# Sensores.net
KiCad netlist of a schematic drawn in EasyEDA Pro
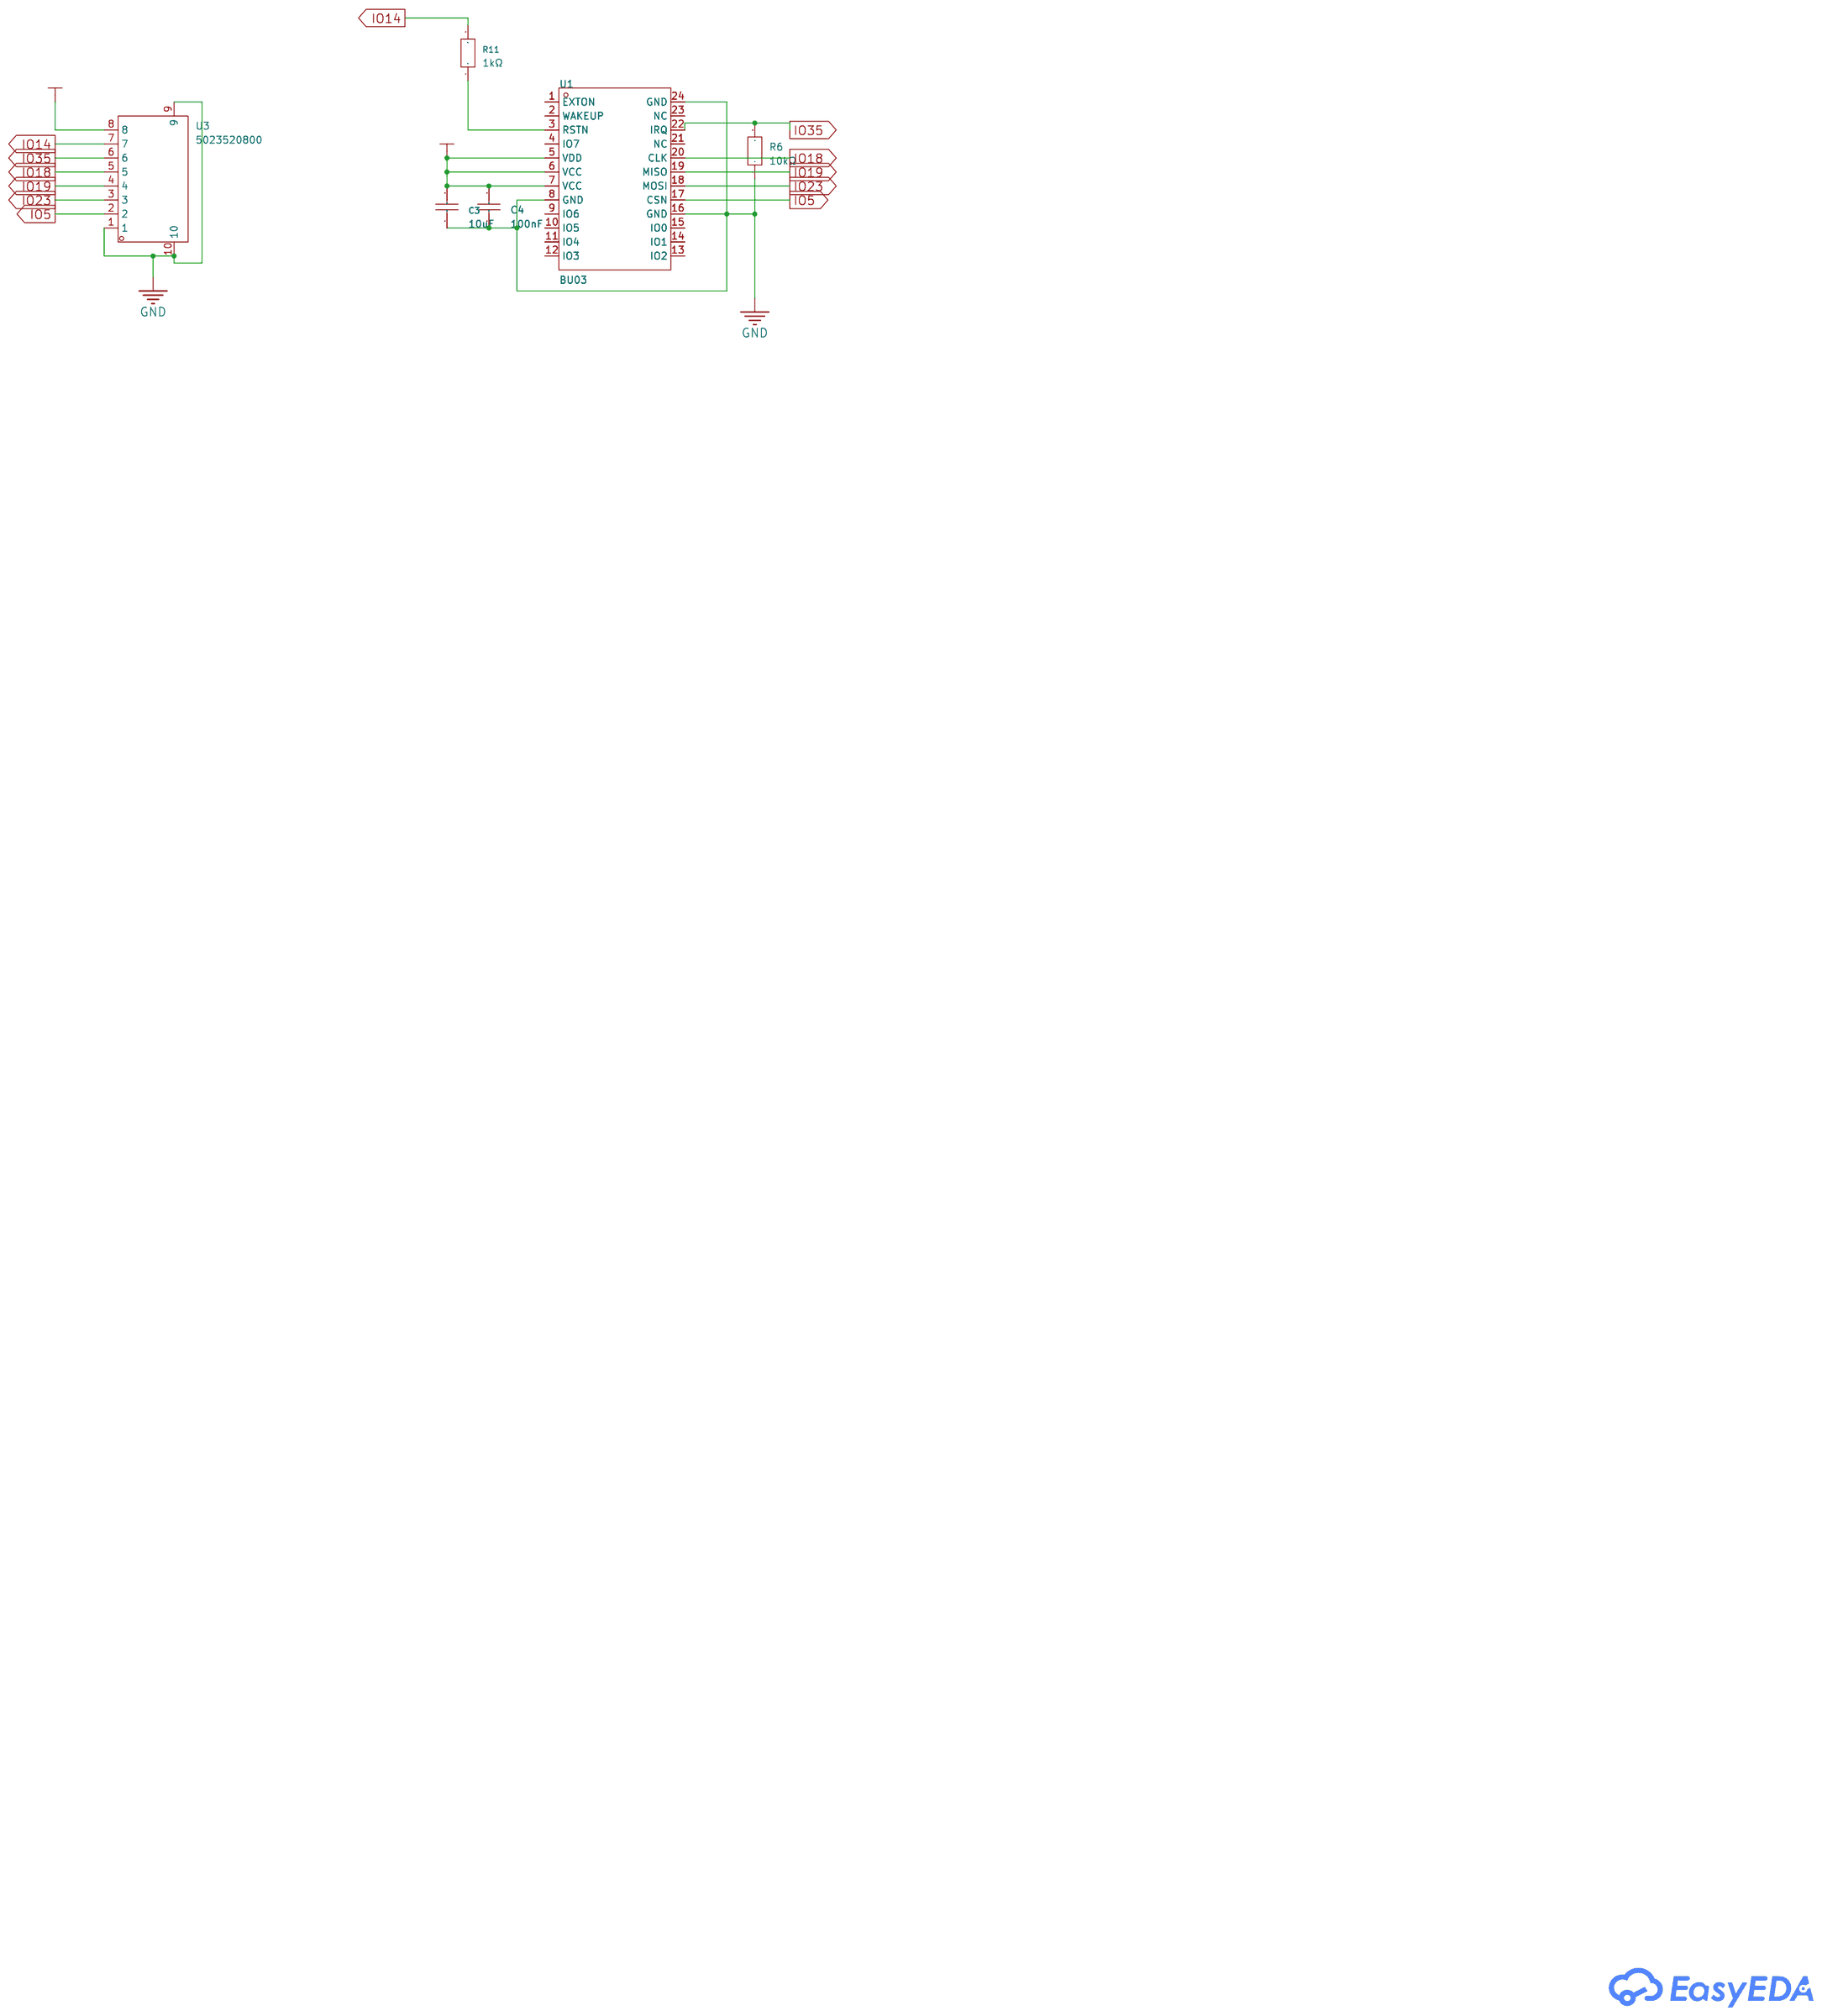
[diagram p0: schematic sheet]

(export (version "E")
  (design (tool "Eeschema 10.0.6"))
  (components
    (comp (ref "C3")
      (value "10uF")
      (footprint "easyedapro:C0805")
      (fields
        (field (name "Manufacturer Part") "CL21A106KPFNNNE")
        (field (name "Manufacturer") "SAMSUNG(三星)")
      )
      (libsource (lib "easyedapro") (part "CL21A106KPFNNNE"))
    )
    (comp (ref "C4")
      (value "100nF")
      (footprint "easyedapro:C0805")
      (description "Capacitance:100nF Tolerance:±5% Tolerance:±5% Voltage Rating:50V Temperature Coefficient:X7R")
      (fields (field (name "Manufacturer Part") "0805B104J500NT") (field (name "Manufacturer") "FH(风华)"))
      (libsource (lib "easyedapro") (part "0805B104J500NT"))
    )
    (comp (ref "R6")
      (value "10kΩ")
      (footprint "easyedapro:R0805")
      (fields (field (name "Manufacturer Part") "ERJP06F1002V") (field (name "Manufacturer") "PANASONIC(松下)"))
      (libsource (lib "easyedapro") (part "ERJP06F1002V"))
    )
    (comp (ref "R11")
      (value "1kΩ")
      (footprint "easyedapro:R0805")
      (fields (field (name "Manufacturer Part") "ERJP06F1001V") (field (name "Manufacturer") "PANASONIC(松下)"))
      (libsource (lib "easyedapro") (part "ERJP06F1001V"))
    )
    (comp (ref "U1")
      (value "BU03")
      (footprint "easyedapro:WIRELM-SMD_BU03")
      (fields (field (name "Manufacturer") "Ai-Thinker(安信可)"))
      (libsource (lib "easyedapro") (part "BU03"))
    )
    (comp (ref "U3")
      (value "5023520800")
      (footprint "easyedapro:CONN-SMD_5023520800")
      (fields (field (name "Manufacturer") "MOLEX"))
      (libsource (lib "easyedapro") (part "5023520800"))
    )
  )
  (nets
    (net (code "1") (name "+3V3") (class "Default")
      (node (ref "C3") (pin "2") (pinfunction "2_2") (pintype "input"))
      (node (ref "C4") (pin "2") (pinfunction "2_2") (pintype "input"))
      (node (ref "U1") (pin "5") (pinfunction "VDD_5") (pintype "unspecified"))
      (node (ref "U1") (pin "6") (pinfunction "VCC_6") (pintype "unspecified"))
      (node (ref "U1") (pin "7") (pinfunction "VCC_7") (pintype "unspecified"))
      (node (ref "U3") (pin "8") (pinfunction "8_8") (pintype "unspecified"))
    )
    (net (code "2") (name "GND") (class "Default")
      (node (ref "C3") (pin "1") (pinfunction "1_1") (pintype "input"))
      (node (ref "C4") (pin "1") (pinfunction "1_1") (pintype "input"))
      (node (ref "R6") (pin "1") (pinfunction "1_1") (pintype "unspecified"))
      (node (ref "U1") (pin "16") (pinfunction "GND_16") (pintype "unspecified"))
      (node (ref "U1") (pin "24") (pinfunction "GND_24") (pintype "unspecified"))
      (node (ref "U1") (pin "8") (pinfunction "GND_8") (pintype "unspecified"))
      (node (ref "U3") (pin "1") (pinfunction "1_1") (pintype "unspecified"))
      (node (ref "U3") (pin "10") (pinfunction "10_10") (pintype "unspecified"))
      (node (ref "U3") (pin "9") (pinfunction "9_9") (pintype "unspecified"))
    )
    (net (code "3") (name "IO5") (class "Default")
      (node (ref "U1") (pin "17") (pinfunction "CSN_17") (pintype "unspecified"))
      (node (ref "U3") (pin "2") (pinfunction "2_2") (pintype "unspecified"))
    )
    (net (code "4") (name "IO14") (class "Default")
      (node (ref "R11") (pin "2") (pinfunction "2_2") (pintype "input"))
      (node (ref "U3") (pin "7") (pinfunction "7_7") (pintype "unspecified"))
    )
    (net (code "5") (name "IO18") (class "Default")
      (node (ref "U1") (pin "20") (pinfunction "CLK_20") (pintype "unspecified"))
      (node (ref "U3") (pin "5") (pinfunction "5_5") (pintype "unspecified"))
    )
    (net (code "6") (name "IO19") (class "Default")
      (node (ref "U1") (pin "19") (pinfunction "MISO_19") (pintype "unspecified"))
      (node (ref "U3") (pin "4") (pinfunction "4_4") (pintype "unspecified"))
    )
    (net (code "7") (name "IO23") (class "Default")
      (node (ref "U1") (pin "18") (pinfunction "MOSI_18") (pintype "unspecified"))
      (node (ref "U3") (pin "3") (pinfunction "3_3") (pintype "unspecified"))
    )
    (net (code "8") (name "IO35") (class "Default")
      (node (ref "R6") (pin "2") (pinfunction "2_2") (pintype "unspecified"))
      (node (ref "U1") (pin "22") (pinfunction "IRQ_22") (pintype "unspecified"))
      (node (ref "U3") (pin "6") (pinfunction "6_6") (pintype "unspecified"))
    )
    (net (code "9") (name "Net-(U1-RSTN)") (class "Default")
      (node (ref "R11") (pin "1") (pinfunction "1_1") (pintype "input"))
      (node (ref "U1") (pin "3") (pinfunction "RSTN_3") (pintype "unspecified"))
    )
    (net (code "10") (name "unconnected-(U1-EXTON-Pad1)") (class "Default")
      (node (ref "U1") (pin "1") (pinfunction "EXTON_1") (pintype "unspecified"))
    )
    (net (code "11") (name "unconnected-(U1-IO0-Pad15)") (class "Default")
      (node (ref "U1") (pin "15") (pinfunction "IO0_15") (pintype "unspecified"))
    )
    (net (code "12") (name "unconnected-(U1-IO1-Pad14)") (class "Default")
      (node (ref "U1") (pin "14") (pinfunction "IO1_14") (pintype "unspecified"))
    )
    (net (code "13") (name "unconnected-(U1-IO2-Pad13)") (class "Default")
      (node (ref "U1") (pin "13") (pinfunction "IO2_13") (pintype "unspecified"))
    )
    (net (code "14") (name "unconnected-(U1-IO3-Pad12)") (class "Default")
      (node (ref "U1") (pin "12") (pinfunction "IO3_12") (pintype "unspecified"))
    )
    (net (code "15") (name "unconnected-(U1-IO4-Pad11)") (class "Default")
      (node (ref "U1") (pin "11") (pinfunction "IO4_11") (pintype "unspecified"))
    )
    (net (code "16") (name "unconnected-(U1-IO5-Pad10)") (class "Default")
      (node (ref "U1") (pin "10") (pinfunction "IO5_10") (pintype "unspecified"))
    )
    (net (code "17") (name "unconnected-(U1-IO6-Pad9)") (class "Default")
      (node (ref "U1") (pin "9") (pinfunction "IO6_9") (pintype "unspecified"))
    )
    (net (code "18") (name "unconnected-(U1-IO7-Pad4)") (class "Default")
      (node (ref "U1") (pin "4") (pinfunction "IO7_4") (pintype "unspecified"))
    )
    (net (code "19") (name "unconnected-(U1-NC-Pad21)") (class "Default")
      (node (ref "U1") (pin "21") (pinfunction "NC_21") (pintype "unspecified"))
    )
    (net (code "20") (name "unconnected-(U1-NC-Pad23)") (class "Default")
      (node (ref "U1") (pin "23") (pinfunction "NC_23") (pintype "unspecified"))
    )
    (net (code "21") (name "unconnected-(U1-WAKEUP-Pad2)") (class "Default")
      (node (ref "U1") (pin "2") (pinfunction "WAKEUP_2") (pintype "unspecified"))
    )
  )
)
